# LED_SEQUENCES.net
KiCad netlist of a schematic drawn in Altium Designer
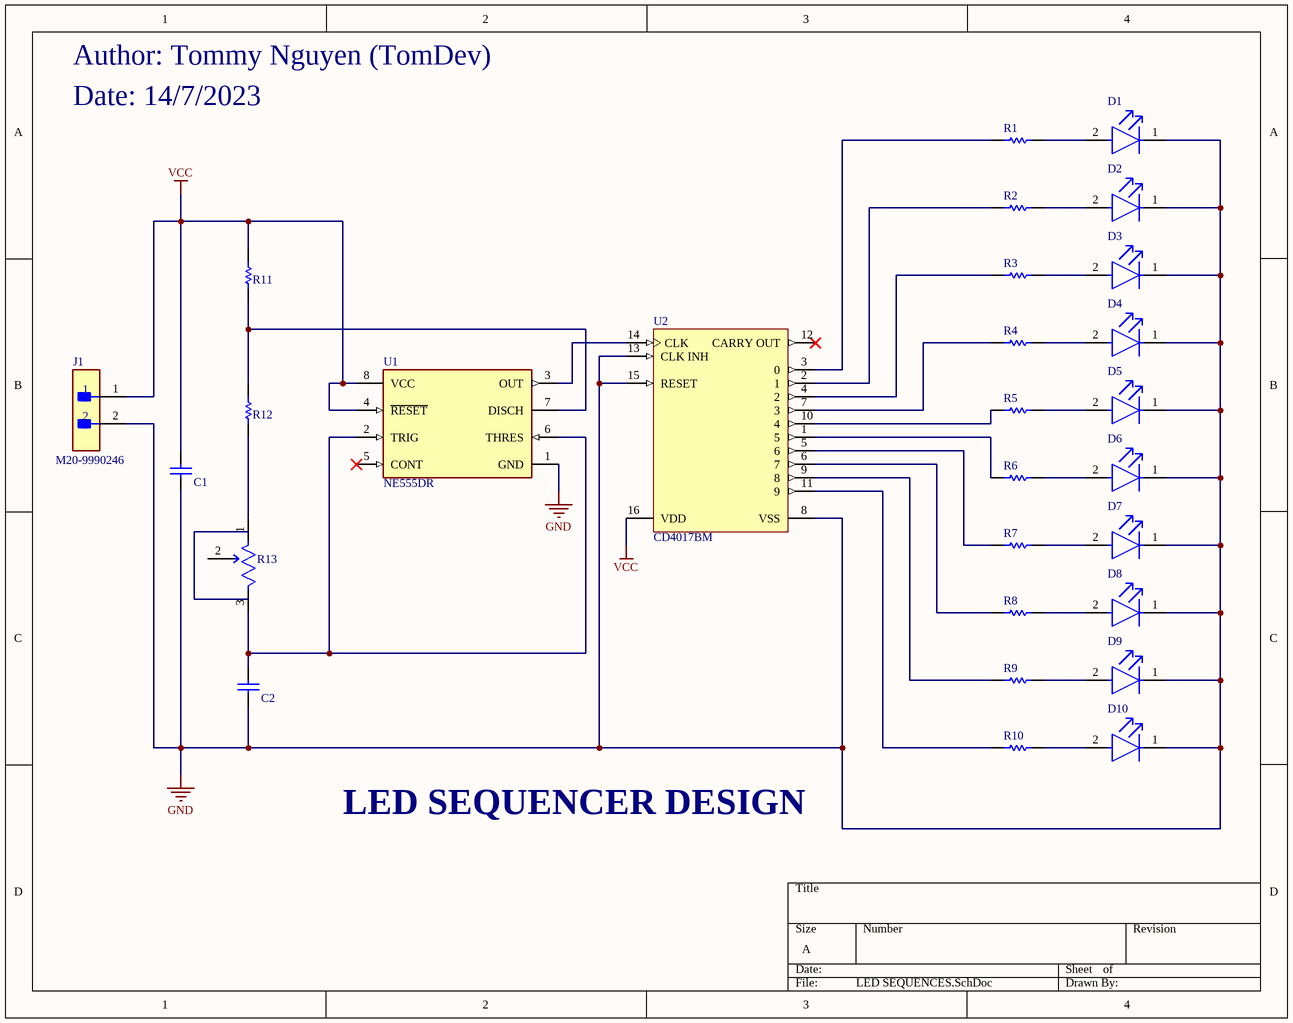
[diagram p0: LED SEQUENCES.SchDoc]

(export (version "E")
  (design (tool "Eeschema 10.0.6"))
  (components
    (comp (ref "C1")
      (value "GRM21BR71H105KA12L")
      (footprint "CAPC2013X135X45LL10T25")
      (fields (field (name "MANUFACTURER") "Murata"))
      (libsource (lib "Altium Content Vault") (part "CAP"))
    )
    (comp (ref "C2")
      (value "GRM21BR71H105KA12L")
      (footprint "CAPC2013X135X45LL10T25")
      (fields (field (name "MANUFACTURER") "Murata"))
      (libsource (lib "Altium Content Vault") (part "CAP"))
    )
    (comp (ref "D1")
      (value "HLMP-1301")
      (footprint "FP-HLMP-1301-MFG")
      (description "LED RED DIFFUSED T-1 T/H")
      (fields
        (field (name "OCTOPART") "https://octopart.com/hlmp-1301-broadcom-71130345")
        (field (name "MANUFACTURER") "Broadcom")
      )
      (libsource (lib "Altium Content Vault") (part "8706943c75ba83719d021d2fdc84c58"))
    )
    (comp (ref "D2")
      (value "HLMP-1301")
      (footprint "FP-HLMP-1301-MFG")
      (description "LED RED DIFFUSED T-1 T/H")
      (fields
        (field (name "OCTOPART") "https://octopart.com/hlmp-1301-broadcom-71130345")
        (field (name "MANUFACTURER") "Broadcom")
      )
      (libsource (lib "Altium Content Vault") (part "8706943c75ba83719d021d2fdc84c58"))
    )
    (comp (ref "D3")
      (value "HLMP-1301")
      (footprint "FP-HLMP-1301-MFG")
      (description "LED RED DIFFUSED T-1 T/H")
      (fields
        (field (name "OCTOPART") "https://octopart.com/hlmp-1301-broadcom-71130345")
        (field (name "MANUFACTURER") "Broadcom")
      )
      (libsource (lib "Altium Content Vault") (part "8706943c75ba83719d021d2fdc84c58"))
    )
    (comp (ref "D4")
      (value "HLMP-1301")
      (footprint "FP-HLMP-1301-MFG")
      (description "LED RED DIFFUSED T-1 T/H")
      (fields
        (field (name "OCTOPART") "https://octopart.com/hlmp-1301-broadcom-71130345")
        (field (name "MANUFACTURER") "Broadcom")
      )
      (libsource (lib "Altium Content Vault") (part "8706943c75ba83719d021d2fdc84c58"))
    )
    (comp (ref "D5")
      (value "HLMP-1301")
      (footprint "FP-HLMP-1301-MFG")
      (description "LED RED DIFFUSED T-1 T/H")
      (fields
        (field (name "OCTOPART") "https://octopart.com/hlmp-1301-broadcom-71130345")
        (field (name "MANUFACTURER") "Broadcom")
      )
      (libsource (lib "Altium Content Vault") (part "8706943c75ba83719d021d2fdc84c58"))
    )
    (comp (ref "D6")
      (value "HLMP-1301")
      (footprint "FP-HLMP-1301-MFG")
      (description "LED RED DIFFUSED T-1 T/H")
      (fields
        (field (name "OCTOPART") "https://octopart.com/hlmp-1301-broadcom-71130345")
        (field (name "MANUFACTURER") "Broadcom")
      )
      (libsource (lib "Altium Content Vault") (part "8706943c75ba83719d021d2fdc84c58"))
    )
    (comp (ref "D7")
      (value "HLMP-1301")
      (footprint "FP-HLMP-1301-MFG")
      (description "LED RED DIFFUSED T-1 T/H")
      (fields
        (field (name "OCTOPART") "https://octopart.com/hlmp-1301-broadcom-71130345")
        (field (name "MANUFACTURER") "Broadcom")
      )
      (libsource (lib "Altium Content Vault") (part "8706943c75ba83719d021d2fdc84c58"))
    )
    (comp (ref "D8")
      (value "HLMP-1301")
      (footprint "FP-HLMP-1301-MFG")
      (description "LED RED DIFFUSED T-1 T/H")
      (fields
        (field (name "OCTOPART") "https://octopart.com/hlmp-1301-broadcom-71130345")
        (field (name "MANUFACTURER") "Broadcom")
      )
      (libsource (lib "Altium Content Vault") (part "8706943c75ba83719d021d2fdc84c58"))
    )
    (comp (ref "D9")
      (value "HLMP-1301")
      (footprint "FP-HLMP-1301-MFG")
      (description "LED RED DIFFUSED T-1 T/H")
      (fields
        (field (name "OCTOPART") "https://octopart.com/hlmp-1301-broadcom-71130345")
        (field (name "MANUFACTURER") "Broadcom")
      )
      (libsource (lib "Altium Content Vault") (part "8706943c75ba83719d021d2fdc84c58"))
    )
    (comp (ref "D10")
      (value "HLMP-1301")
      (footprint "FP-HLMP-1301-MFG")
      (description "LED RED DIFFUSED T-1 T/H")
      (fields
        (field (name "OCTOPART") "https://octopart.com/hlmp-1301-broadcom-71130345")
        (field (name "MANUFACTURER") "Broadcom")
      )
      (libsource (lib "Altium Content Vault") (part "8706943c75ba83719d021d2fdc84c58"))
    )
    (comp (ref "J1")
      (value "M20-9990246")
      (footprint "FP-M20-9990246-MFG")
      (description "Connector Header Through Hole 2 position 0.100\" (2.54mm)")
      (fields (field (name "OCTOPART") "https://octopart.com/m20-9990246-harwin-2590635"))
      (libsource (lib "Altium Content Vault") (part "3bc925449376181038e59eaffc5286c"))
    )
    (comp (ref "R1")
      (value "RC0805FR-071KL")
      (footprint "RESC2013X60X35ML10T20")
      (description "Chip Resistor, 1 KOhm, +/- 1%, 125 mW, -55 to 155 degC, 0805 (2012 Metric), RoHS, Tape and Reel")
      (fields (field (name "TOLERANCE") "1%") (field (name "MANUFACTURER") "Yageo"))
      (libsource (lib "Altium Content Vault") (part "RES-2"))
    )
    (comp (ref "R2")
      (value "RC0805FR-071KL")
      (footprint "RESC2013X60X35ML10T20")
      (description "Chip Resistor, 1 KOhm, +/- 1%, 125 mW, -55 to 155 degC, 0805 (2012 Metric), RoHS, Tape and Reel")
      (fields (field (name "TOLERANCE") "1%") (field (name "MANUFACTURER") "Yageo"))
      (libsource (lib "Altium Content Vault") (part "RES-2"))
    )
    (comp (ref "R3")
      (value "RC0805FR-071KL")
      (footprint "RESC2013X60X35ML10T20")
      (description "Chip Resistor, 1 KOhm, +/- 1%, 125 mW, -55 to 155 degC, 0805 (2012 Metric), RoHS, Tape and Reel")
      (fields (field (name "TOLERANCE") "1%") (field (name "MANUFACTURER") "Yageo"))
      (libsource (lib "Altium Content Vault") (part "RES-2"))
    )
    (comp (ref "R4")
      (value "RC0805FR-071KL")
      (footprint "RESC2013X60X35ML10T20")
      (description "Chip Resistor, 1 KOhm, +/- 1%, 125 mW, -55 to 155 degC, 0805 (2012 Metric), RoHS, Tape and Reel")
      (fields (field (name "TOLERANCE") "1%") (field (name "MANUFACTURER") "Yageo"))
      (libsource (lib "Altium Content Vault") (part "RES-2"))
    )
    (comp (ref "R5")
      (value "RC0805FR-071KL")
      (footprint "RESC2013X60X35ML10T20")
      (description "Chip Resistor, 1 KOhm, +/- 1%, 125 mW, -55 to 155 degC, 0805 (2012 Metric), RoHS, Tape and Reel")
      (fields (field (name "TOLERANCE") "1%") (field (name "MANUFACTURER") "Yageo"))
      (libsource (lib "Altium Content Vault") (part "RES-2"))
    )
    (comp (ref "R6")
      (value "RC0805FR-071KL")
      (footprint "RESC2013X60X35ML10T20")
      (description "Chip Resistor, 1 KOhm, +/- 1%, 125 mW, -55 to 155 degC, 0805 (2012 Metric), RoHS, Tape and Reel")
      (fields (field (name "TOLERANCE") "1%") (field (name "MANUFACTURER") "Yageo"))
      (libsource (lib "Altium Content Vault") (part "RES-2"))
    )
    (comp (ref "R7")
      (value "RC0805FR-071KL")
      (footprint "RESC2013X60X35ML10T20")
      (description "Chip Resistor, 1 KOhm, +/- 1%, 125 mW, -55 to 155 degC, 0805 (2012 Metric), RoHS, Tape and Reel")
      (fields (field (name "TOLERANCE") "1%") (field (name "MANUFACTURER") "Yageo"))
      (libsource (lib "Altium Content Vault") (part "RES-2"))
    )
    (comp (ref "R8")
      (value "RC0805FR-071KL")
      (footprint "RESC2013X60X35ML10T20")
      (description "Chip Resistor, 1 KOhm, +/- 1%, 125 mW, -55 to 155 degC, 0805 (2012 Metric), RoHS, Tape and Reel")
      (fields (field (name "TOLERANCE") "1%") (field (name "MANUFACTURER") "Yageo"))
      (libsource (lib "Altium Content Vault") (part "RES-2"))
    )
    (comp (ref "R9")
      (value "RC0805FR-071KL")
      (footprint "RESC2013X60X35ML10T20")
      (description "Chip Resistor, 1 KOhm, +/- 1%, 125 mW, -55 to 155 degC, 0805 (2012 Metric), RoHS, Tape and Reel")
      (fields (field (name "TOLERANCE") "1%") (field (name "MANUFACTURER") "Yageo"))
      (libsource (lib "Altium Content Vault") (part "RES-2"))
    )
    (comp (ref "R10")
      (value "RC0805FR-071KL")
      (footprint "RESC2013X60X35ML10T20")
      (description "Chip Resistor, 1 KOhm, +/- 1%, 125 mW, -55 to 155 degC, 0805 (2012 Metric), RoHS, Tape and Reel")
      (fields (field (name "TOLERANCE") "1%") (field (name "MANUFACTURER") "Yageo"))
      (libsource (lib "Altium Content Vault") (part "RES-2"))
    )
    (comp (ref "R11")
      (value "RC0805FR-071KL")
      (footprint "RESC2013X60X35ML10T20")
      (description "Chip Resistor, 1 KOhm, +/- 1%, 125 mW, -55 to 155 degC, 0805 (2012 Metric), RoHS, Tape and Reel")
      (fields (field (name "TOLERANCE") "1%") (field (name "MANUFACTURER") "Yageo"))
      (libsource (lib "Altium Content Vault") (part "RES-2"))
    )
    (comp (ref "R12")
      (value "RC0805FR-071KL")
      (footprint "RESC2013X60X35ML10T20")
      (description "Chip Resistor, 1 KOhm, +/- 1%, 125 mW, -55 to 155 degC, 0805 (2012 Metric), RoHS, Tape and Reel")
      (fields (field (name "TOLERANCE") "1%") (field (name "MANUFACTURER") "Yageo"))
      (libsource (lib "Altium Content Vault") (part "RES-2"))
    )
    (comp (ref "R13")
      (value "3386P-1-104LF")
      (footprint "FP-3386P-MFG")
      (description "TRIMMER 100K OHM 0.5W PC PIN TOP")
      (fields (field (name "TOLERANCE") "10%"))
      (libsource (lib "Altium Content Vault") (part "13357d81287629c2fd191d242cfa50c"))
    )
    (comp (ref "U1")
      (value "NE555DR")
      (footprint "FP-D0008A-IPC_A")
      (description "IC OSC SGL TIMER 100KHZ 8-SOIC")
      (libsource (lib "Altium Content Vault") (part "a29bba90211dec1890110b94dad7d53"))
    )
    (comp (ref "U2")
      (value "CD4017BM")
      (footprint "D0016A_N")
      (description "CMOS Decade Counter with 10 Decoded Outputs, D0016A, TUBE")
      (fields
        (field (name "GENERIC PART NUMBER") "CD4017B")
        (field (name "MANUFACTURER") "Texas Instruments")
      )
      (libsource (lib "Altium Content Vault") (part "TI-CD4017B-16"))
    )
  )
  (nets
    (net (code "1") (name "GND") (class "Default")
      (node (ref "C1") (pin "1") (pinfunction "1_1") (pintype "passive"))
      (node (ref "C2") (pin "1") (pinfunction "1_1") (pintype "passive"))
      (node (ref "D1") (pin "1") (pinfunction "C_1") (pintype "passive"))
      (node (ref "D10") (pin "1") (pinfunction "C_1") (pintype "passive"))
      (node (ref "D2") (pin "1") (pinfunction "C_1") (pintype "passive"))
      (node (ref "D3") (pin "1") (pinfunction "C_1") (pintype "passive"))
      (node (ref "D4") (pin "1") (pinfunction "C_1") (pintype "passive"))
      (node (ref "D5") (pin "1") (pinfunction "C_1") (pintype "passive"))
      (node (ref "D6") (pin "1") (pinfunction "C_1") (pintype "passive"))
      (node (ref "D7") (pin "1") (pinfunction "C_1") (pintype "passive"))
      (node (ref "D8") (pin "1") (pinfunction "C_1") (pintype "passive"))
      (node (ref "D9") (pin "1") (pinfunction "C_1") (pintype "passive"))
      (node (ref "J1") (pin "2") (pinfunction "2_2") (pintype "passive"))
      (node (ref "U1") (pin "1") (pinfunction "GND_1") (pintype "power_in"))
      (node (ref "U2") (pin "13") (pinfunction "CLK_INH_13") (pintype "input"))
      (node (ref "U2") (pin "15") (pinfunction "RESET_15") (pintype "input"))
      (node (ref "U2") (pin "8") (pinfunction "VSS_8") (pintype "power_in"))
    )
    (net (code "2") (name "Net-(D1-A)") (class "Default")
      (node (ref "D1") (pin "2") (pinfunction "A_2") (pintype "passive"))
      (node (ref "R1") (pin "2") (pinfunction "2_2") (pintype "passive"))
    )
    (net (code "3") (name "Net-(D2-A)") (class "Default")
      (node (ref "D2") (pin "2") (pinfunction "A_2") (pintype "passive"))
      (node (ref "R2") (pin "2") (pinfunction "2_2") (pintype "passive"))
    )
    (net (code "4") (name "Net-(D3-A)") (class "Default")
      (node (ref "D3") (pin "2") (pinfunction "A_2") (pintype "passive"))
      (node (ref "R3") (pin "2") (pinfunction "2_2") (pintype "passive"))
    )
    (net (code "5") (name "Net-(D4-A)") (class "Default")
      (node (ref "D4") (pin "2") (pinfunction "A_2") (pintype "passive"))
      (node (ref "R4") (pin "2") (pinfunction "2_2") (pintype "passive"))
    )
    (net (code "6") (name "Net-(D5-A)") (class "Default")
      (node (ref "D5") (pin "2") (pinfunction "A_2") (pintype "passive"))
      (node (ref "R5") (pin "2") (pinfunction "2_2") (pintype "passive"))
    )
    (net (code "7") (name "Net-(D6-A)") (class "Default")
      (node (ref "D6") (pin "2") (pinfunction "A_2") (pintype "passive"))
      (node (ref "R6") (pin "2") (pinfunction "2_2") (pintype "passive"))
    )
    (net (code "8") (name "Net-(D7-A)") (class "Default")
      (node (ref "D7") (pin "2") (pinfunction "A_2") (pintype "passive"))
      (node (ref "R7") (pin "2") (pinfunction "2_2") (pintype "passive"))
    )
    (net (code "9") (name "Net-(D8-A)") (class "Default")
      (node (ref "D8") (pin "2") (pinfunction "A_2") (pintype "passive"))
      (node (ref "R8") (pin "2") (pinfunction "2_2") (pintype "passive"))
    )
    (net (code "10") (name "Net-(D9-A)") (class "Default")
      (node (ref "D9") (pin "2") (pinfunction "A_2") (pintype "passive"))
      (node (ref "R9") (pin "2") (pinfunction "2_2") (pintype "passive"))
    )
    (net (code "11") (name "Net-(D10-A)") (class "Default")
      (node (ref "D10") (pin "2") (pinfunction "A_2") (pintype "passive"))
      (node (ref "R10") (pin "2") (pinfunction "2_2") (pintype "passive"))
    )
    (net (code "12") (name "Net-(R13-CCW)") (class "Default")
      (node (ref "R12") (pin "1") (pinfunction "1_1") (pintype "passive"))
      (node (ref "R13") (pin "1") (pinfunction "CCW_1") (pintype "passive"))
    )
    (net (code "13") (name "Net-(R13-CW)") (class "Default")
      (node (ref "C2") (pin "2") (pinfunction "2_2") (pintype "passive"))
      (node (ref "R13") (pin "3") (pinfunction "CW_3") (pintype "passive"))
      (node (ref "U1") (pin "2") (pinfunction "TRIG_2") (pintype "input"))
      (node (ref "U1") (pin "6") (pinfunction "THRES_6") (pintype "input"))
    )
    (net (code "14") (name "Net-(U1-DISCH)") (class "Default")
      (node (ref "R11") (pin "1") (pinfunction "1_1") (pintype "passive"))
      (node (ref "R12") (pin "2") (pinfunction "2_2") (pintype "passive"))
      (node (ref "U1") (pin "7") (pinfunction "DISCH_7") (pintype "open_collector"))
    )
    (net (code "15") (name "Net-(U1-OUT)") (class "Default")
      (node (ref "U1") (pin "3") (pinfunction "OUT_3") (pintype "output"))
      (node (ref "U2") (pin "14") (pinfunction "CLK_14") (pintype "input"))
    )
    (net (code "16") (name "Net-(U2-0)") (class "Default")
      (node (ref "R1") (pin "1") (pinfunction "1_1") (pintype "passive"))
      (node (ref "U2") (pin "3") (pinfunction "0_3") (pintype "output"))
    )
    (net (code "17") (name "Net-(U2-1)") (class "Default")
      (node (ref "R2") (pin "1") (pinfunction "1_1") (pintype "passive"))
      (node (ref "U2") (pin "2") (pinfunction "1_2") (pintype "output"))
    )
    (net (code "18") (name "Net-(U2-2)") (class "Default")
      (node (ref "R3") (pin "1") (pinfunction "1_1") (pintype "passive"))
      (node (ref "U2") (pin "4") (pinfunction "2_4") (pintype "output"))
    )
    (net (code "19") (name "Net-(U2-3)") (class "Default")
      (node (ref "R4") (pin "1") (pinfunction "1_1") (pintype "passive"))
      (node (ref "U2") (pin "7") (pinfunction "3_7") (pintype "output"))
    )
    (net (code "20") (name "Net-(U2-4)") (class "Default")
      (node (ref "R5") (pin "1") (pinfunction "1_1") (pintype "passive"))
      (node (ref "U2") (pin "10") (pinfunction "4_10") (pintype "output"))
    )
    (net (code "21") (name "Net-(U2-5)") (class "Default")
      (node (ref "R6") (pin "1") (pinfunction "1_1") (pintype "passive"))
      (node (ref "U2") (pin "1") (pinfunction "5_1") (pintype "output"))
    )
    (net (code "22") (name "Net-(U2-6)") (class "Default")
      (node (ref "R7") (pin "1") (pinfunction "1_1") (pintype "passive"))
      (node (ref "U2") (pin "5") (pinfunction "6_5") (pintype "output"))
    )
    (net (code "23") (name "Net-(U2-7)") (class "Default")
      (node (ref "R8") (pin "1") (pinfunction "1_1") (pintype "passive"))
      (node (ref "U2") (pin "6") (pinfunction "7_6") (pintype "output"))
    )
    (net (code "24") (name "Net-(U2-8)") (class "Default")
      (node (ref "R9") (pin "1") (pinfunction "1_1") (pintype "passive"))
      (node (ref "U2") (pin "9") (pinfunction "8_9") (pintype "output"))
    )
    (net (code "25") (name "Net-(U2-9)") (class "Default")
      (node (ref "R10") (pin "1") (pinfunction "1_1") (pintype "passive"))
      (node (ref "U2") (pin "11") (pinfunction "9_11") (pintype "output"))
    )
    (net (code "26") (name "VCC") (class "Default")
      (node (ref "C1") (pin "2") (pinfunction "2_2") (pintype "passive"))
      (node (ref "J1") (pin "1") (pinfunction "1_1") (pintype "passive"))
      (node (ref "R11") (pin "2") (pinfunction "2_2") (pintype "passive"))
      (node (ref "U1") (pin "4") (pinfunction "~{RESET}_4") (pintype "input"))
      (node (ref "U1") (pin "8") (pinfunction "VCC_8") (pintype "power_in"))
      (node (ref "U2") (pin "16") (pinfunction "VDD_16") (pintype "power_in"))
    )
    (net (code "27") (name "unconnected-(R13-WIPER-Pad2)") (class "Default")
      (node (ref "R13") (pin "2") (pinfunction "WIPER_2") (pintype "passive"))
    )
    (net (code "28") (name "unconnected-(U1-CONT-Pad5)") (class "Default")
      (node (ref "U1") (pin "5") (pinfunction "CONT_5") (pintype "input+no_connect"))
    )
    (net (code "29") (name "unconnected-(U2-CARRY_OUT-Pad12)") (class "Default")
      (node (ref "U2") (pin "12") (pinfunction "CARRY_OUT_12") (pintype "output+no_connect"))
    )
  )
)
